# oblatkovac.net
KiCad netlist of a schematic drawn in EAGLE
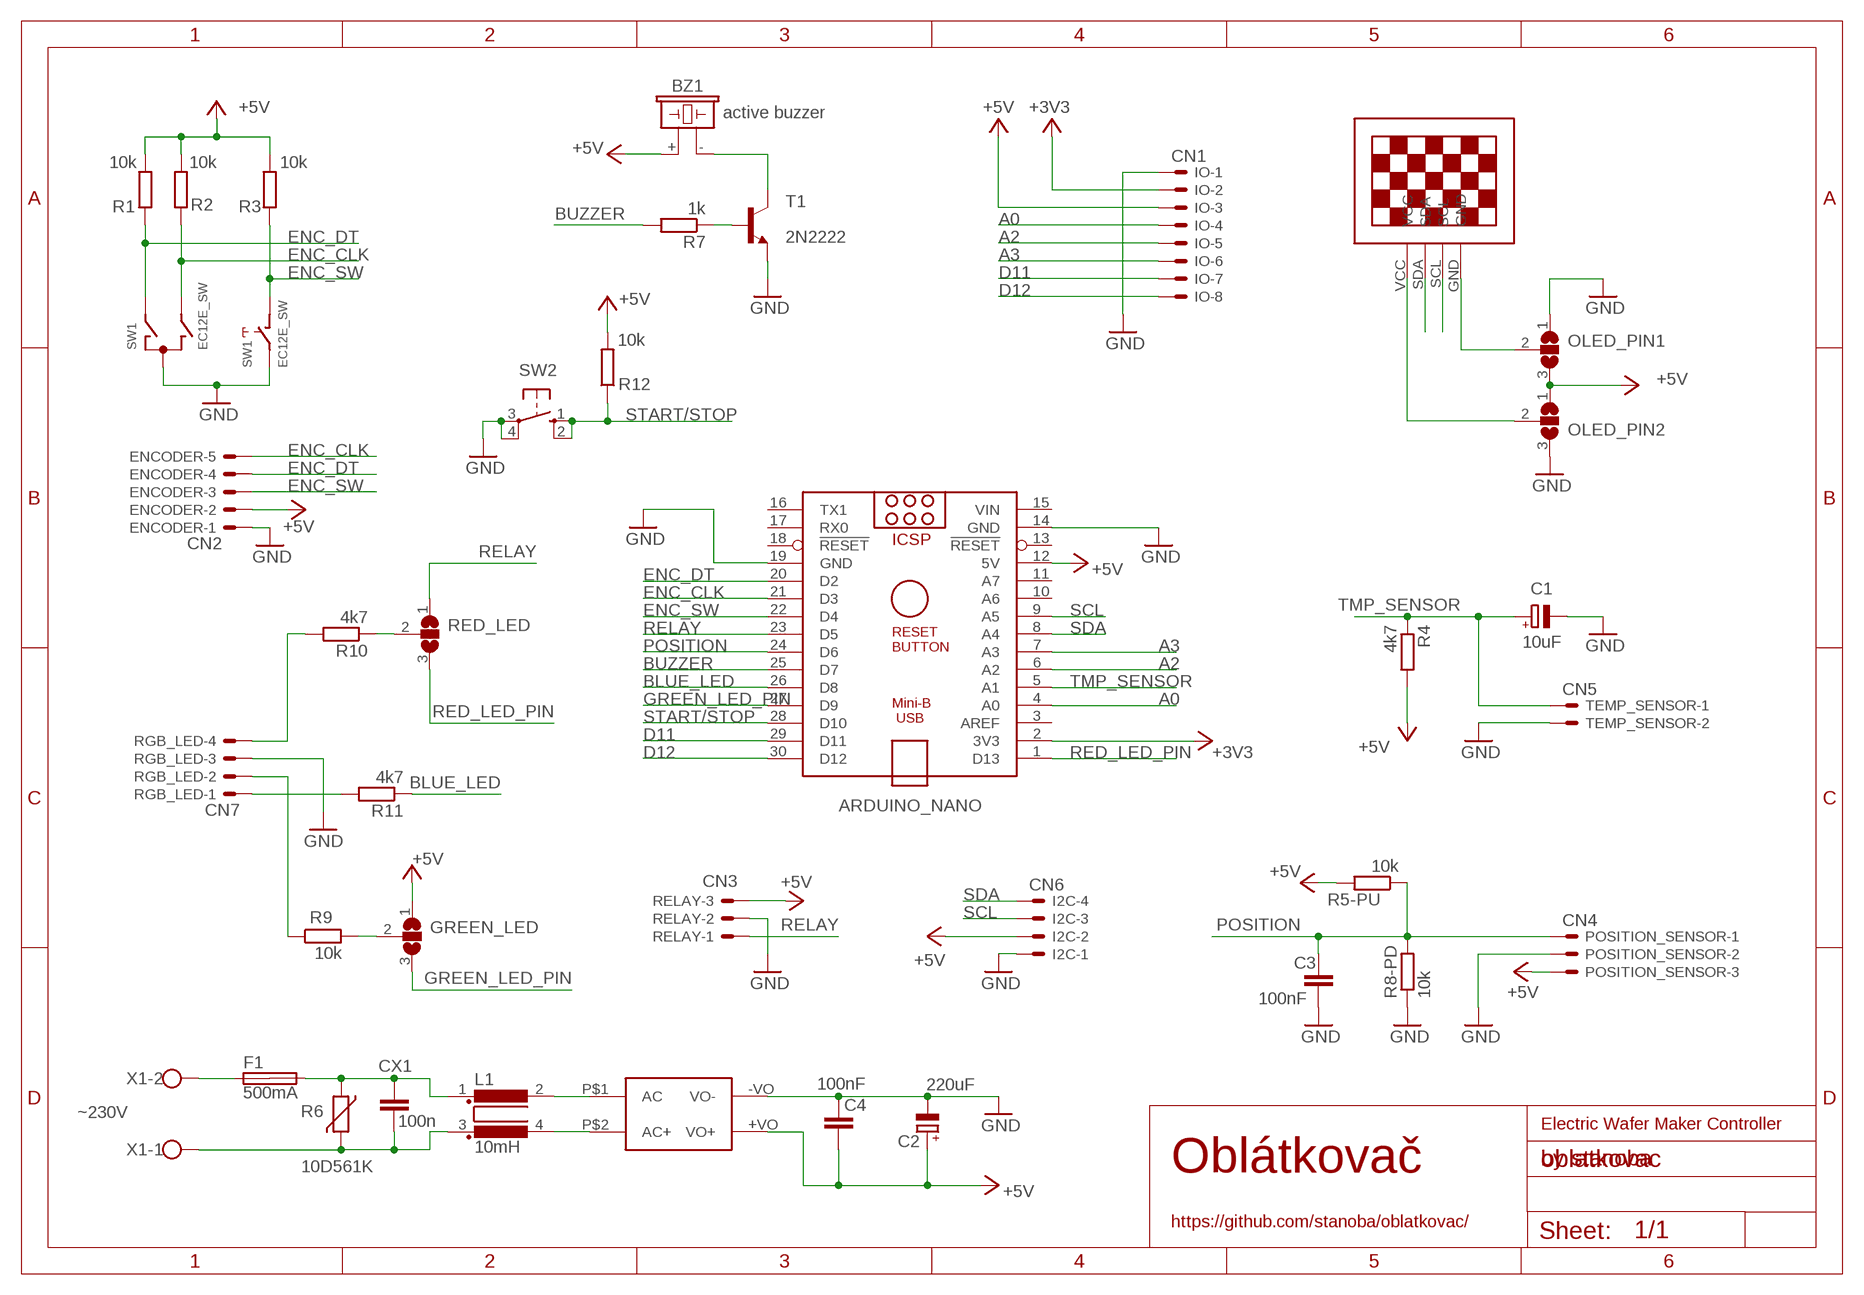
[diagram p0: schematic, sheet 1]

(export (version "E")
  (design (tool "Eeschema 10.0.6"))
  (components
    (comp (ref "ARDUINO_NANO")
      (value "ARDUINO_NANO")
      (footprint "eagle-import:ARDUINO_NANO")
      (libsource (lib "eagle-import") (part "ARDUINO_NANO"))
    )
    (comp (ref "BZ1")
      (value "active buzzer")
      (footprint "eagle-import:F_CM12P")
      (libsource (lib "eagle-import") (part "F/CM12P"))
    )
    (comp (ref "C1")
      (value "10uF")
      (footprint "eagle-import:E5-6")
      (libsource (lib "eagle-import") (part "CPOL-EUE5-6"))
    )
    (comp (ref "C2")
      (value "220uF")
      (footprint "eagle-import:E5-10,5")
      (libsource (lib "eagle-import") (part "CPOL-EUE5-10.5"))
    )
    (comp (ref "C3")
      (value "100nF")
      (footprint "eagle-import:C050-024X044")
      (libsource (lib "eagle-import") (part "C-EU050-024X044"))
    )
    (comp (ref "C4")
      (value "100nF")
      (footprint "eagle-import:C050-024X044")
      (libsource (lib "eagle-import") (part "C-EU050-024X044"))
    )
    (comp (ref "CX1")
      (value "100n")
      (footprint "eagle-import:XC10B6")
      (libsource (lib "eagle-import") (part "CXXC10B6"))
    )
    (comp (ref "ENCODER")
      (value "CN2")
      (footprint "eagle-import:JST-XH-05-PACKAGE-LONG-PAD")
      (libsource (lib "eagle-import") (part "JST-XH-05-PIN-LONG-PAD"))
    )
    (comp (ref "F1")
      (value "500mA")
      (footprint "eagle-import:SHK20L")
      (libsource (lib "eagle-import") (part "SHK20L"))
    )
    (comp (ref "GREEN_LED")
      (value "SJ2W")
      (footprint "eagle-import:SJ_2")
      (libsource (lib "eagle-import") (part "SJ2W"))
    )
    (comp (ref "I2C")
      (value "CN6")
      (footprint "eagle-import:JST-XH-04-PACKAGE-LONG-PAD")
      (libsource (lib "eagle-import") (part "JST-XH-04-PIN-LONG-PAD"))
    )
    (comp (ref "IO")
      (value "CN1")
      (footprint "eagle-import:JST-XH-08-PACKAGE-LONG-PAD")
      (libsource (lib "eagle-import") (part "JST-XH-08-PIN-LONG-PAD"))
    )
    (comp (ref "L1")
      (value "10mH")
      (footprint "eagle-import:B2")
      (libsource (lib "eagle-import") (part "R1405XB2"))
    )
    (comp (ref "OLED_PIN1")
      (value "SJ2W")
      (footprint "eagle-import:SJ_2")
      (libsource (lib "eagle-import") (part "SJ2W"))
    )
    (comp (ref "OLED_PIN2")
      (value "SJ2W")
      (footprint "eagle-import:SJ_2")
      (libsource (lib "eagle-import") (part "SJ2W"))
    )
    (comp (ref "POSITION_SENSOR")
      (value "CN4")
      (footprint "eagle-import:JST-XH-03-PACKAGE-LONG-PAD")
      (libsource (lib "eagle-import") (part "JST-XH-03-PIN-LONG-PAD"))
    )
    (comp (ref "R1")
      (value "10k")
      (footprint "eagle-import:0207_10")
      (libsource (lib "eagle-import") (part "R-EU_0207/10"))
    )
    (comp (ref "R2")
      (value "10k")
      (footprint "eagle-import:0207_10")
      (libsource (lib "eagle-import") (part "R-EU_0207/10"))
    )
    (comp (ref "R3")
      (value "10k")
      (footprint "eagle-import:0207_10")
      (libsource (lib "eagle-import") (part "R-EU_0207/10"))
    )
    (comp (ref "R4")
      (value "4k7")
      (footprint "eagle-import:0207_10")
      (libsource (lib "eagle-import") (part "R-EU_0207/10"))
    )
    (comp (ref "R5-PU")
      (value "10k")
      (footprint "eagle-import:0207_10")
      (libsource (lib "eagle-import") (part "R-EU_0207/10"))
    )
    (comp (ref "R6")
      (value "10D561K")
      (footprint "eagle-import:R-7,5")
      (libsource (lib "eagle-import") (part "VARISTOR-7,5"))
    )
    (comp (ref "R7")
      (value "1k")
      (footprint "eagle-import:0207_10")
      (libsource (lib "eagle-import") (part "R-EU_0207/10"))
    )
    (comp (ref "R8-PD")
      (value "10k")
      (footprint "eagle-import:0207_10")
      (libsource (lib "eagle-import") (part "R-EU_0207/10"))
    )
    (comp (ref "R9")
      (value "10k")
      (footprint "eagle-import:0207_10")
      (libsource (lib "eagle-import") (part "R-EU_0207/10"))
    )
    (comp (ref "R10")
      (value "4k7")
      (footprint "eagle-import:0207_10")
      (libsource (lib "eagle-import") (part "R-EU_0207/10"))
    )
    (comp (ref "R11")
      (value "4k7")
      (footprint "eagle-import:0207_10")
      (libsource (lib "eagle-import") (part "R-EU_0207/10"))
    )
    (comp (ref "R12")
      (value "10k")
      (footprint "eagle-import:0207_10")
      (libsource (lib "eagle-import") (part "R-EU_0207/10"))
    )
    (comp (ref "RED_LED")
      (value "SJ2W")
      (footprint "eagle-import:SJ_2")
      (libsource (lib "eagle-import") (part "SJ2W"))
    )
    (comp (ref "RELAY")
      (value "CN3")
      (footprint "eagle-import:JST-XH-03-PACKAGE-LONG-PAD")
      (libsource (lib "eagle-import") (part "JST-XH-03-PIN-LONG-PAD"))
    )
    (comp (ref "RGB_LED")
      (value "CN7")
      (footprint "eagle-import:JST-XH-04-PACKAGE-LONG-PAD")
      (libsource (lib "eagle-import") (part "JST-XH-04-PIN-LONG-PAD"))
    )
    (comp (ref "SW1")
      (value "EC12E_SW")
      (footprint "eagle-import:ALPS_EC12E_SW")
      (fields (field (name "MPN") "EC12E2424407"))
      (libsource (lib "eagle-import") (part "EC12E_SW"))
    )
    (comp (ref "SW2")
      (value "10-XX")
      (footprint "eagle-import:B3F-10XX")
      (fields (field (name "MPN") "B3F-1000"))
      (libsource (lib "eagle-import") (part "10-XX"))
    )
    (comp (ref "T1")
      (value "2N2222")
      (footprint "eagle-import:TO92-EBC")
      (libsource (lib "eagle-import") (part "-NPN-TO92-EBC"))
    )
    (comp (ref "TEMP_SENSOR")
      (value "CN5")
      (footprint "eagle-import:JST-XH-02-PACKAGE-LONG-PAD")
      (libsource (lib "eagle-import") (part "JST-XH-02-PIN-LONG-PAD"))
    )
    (comp (ref "U$1")
      (value "13\"OLED13\"OLED")
      (footprint "eagle-import:1.3_OLED")
      (libsource (lib "eagle-import") (part "13{dblquote}OLED13{dblquote}OLED"))
    )
    (comp (ref "U$2")
      (value "HLK-5M05")
      (footprint "eagle-import:HLK-5M05")
      (libsource (lib "eagle-import") (part "HLK-5M05"))
    )
    (comp (ref "X1")
      (value "~230V")
      (footprint "eagle-import:W237-102")
      (fields (field (name "MPN") "237-102"))
      (libsource (lib "eagle-import") (part "W237-102"))
    )
  )
  (nets
    (net (code "1") (name "+3V3") (class "Default")
      (node (ref "ARDUINO_NANO") (pin "2") (pinfunction "3V3_2") (pintype "output"))
      (node (ref "IO") (pin "2") (pinfunction "S_2") (pintype "passive"))
    )
    (net (code "2") (name "+5V") (class "Default")
      (node (ref "ARDUINO_NANO") (pin "12") (pinfunction "5V_12") (pintype "power_in"))
      (node (ref "BZ1") (pin "+") (pinfunction "1_+") (pintype "passive"))
      (node (ref "C2") (pin "+") (pinfunction "+_+") (pintype "passive"))
      (node (ref "C4") (pin "2") (pinfunction "2_2") (pintype "passive"))
      (node (ref "ENCODER") (pin "2") (pinfunction "S_2") (pintype "passive"))
      (node (ref "GREEN_LED") (pin "1") (pinfunction "1_1") (pintype "passive"))
      (node (ref "I2C") (pin "2") (pinfunction "S_2") (pintype "passive"))
      (node (ref "IO") (pin "3") (pinfunction "S_3") (pintype "passive"))
      (node (ref "OLED_PIN1") (pin "3") (pinfunction "3_3") (pintype "passive"))
      (node (ref "OLED_PIN2") (pin "1") (pinfunction "1_1") (pintype "passive"))
      (node (ref "POSITION_SENSOR") (pin "3") (pinfunction "S_3") (pintype "passive"))
      (node (ref "R1") (pin "2") (pinfunction "2_2") (pintype "passive"))
      (node (ref "R12") (pin "2") (pinfunction "2_2") (pintype "passive"))
      (node (ref "R2") (pin "2") (pinfunction "2_2") (pintype "passive"))
      (node (ref "R3") (pin "2") (pinfunction "2_2") (pintype "passive"))
      (node (ref "R4") (pin "2") (pinfunction "2_2") (pintype "passive"))
      (node (ref "R5-PU") (pin "2") (pinfunction "2_2") (pintype "passive"))
      (node (ref "RELAY") (pin "3") (pinfunction "S_3") (pintype "passive"))
      (node (ref "U$2") (pin "+VO") (pinfunction "VO+_+VO") (pintype "bidirectional"))
    )
    (net (code "3") (name "/A0") (class "Default")
      (node (ref "ARDUINO_NANO") (pin "4") (pinfunction "A0_4") (pintype "bidirectional"))
      (node (ref "IO") (pin "4") (pinfunction "S_4") (pintype "passive"))
    )
    (net (code "4") (name "/A2") (class "Default")
      (node (ref "ARDUINO_NANO") (pin "6") (pinfunction "A2_6") (pintype "bidirectional"))
      (node (ref "IO") (pin "5") (pinfunction "S_5") (pintype "passive"))
    )
    (net (code "5") (name "/A3") (class "Default")
      (node (ref "ARDUINO_NANO") (pin "7") (pinfunction "A3_7") (pintype "bidirectional"))
      (node (ref "IO") (pin "6") (pinfunction "S_6") (pintype "passive"))
    )
    (net (code "6") (name "/BLUE_LED") (class "Default")
      (node (ref "ARDUINO_NANO") (pin "26") (pinfunction "D8_26") (pintype "bidirectional"))
      (node (ref "R11") (pin "1") (pinfunction "1_1") (pintype "passive"))
    )
    (net (code "7") (name "/BUZZER") (class "Default")
      (node (ref "ARDUINO_NANO") (pin "25") (pinfunction "D7_25") (pintype "bidirectional"))
      (node (ref "R7") (pin "2") (pinfunction "2_2") (pintype "passive"))
    )
    (net (code "8") (name "/D11") (class "Default")
      (node (ref "ARDUINO_NANO") (pin "29") (pinfunction "D11_29") (pintype "bidirectional"))
      (node (ref "IO") (pin "7") (pinfunction "S_7") (pintype "passive"))
    )
    (net (code "9") (name "/D12") (class "Default")
      (node (ref "ARDUINO_NANO") (pin "30") (pinfunction "D12_30") (pintype "bidirectional"))
      (node (ref "IO") (pin "8") (pinfunction "S_8") (pintype "passive"))
    )
    (net (code "10") (name "/ENC_CLK") (class "Default")
      (node (ref "ARDUINO_NANO") (pin "21") (pinfunction "D3_21") (pintype "bidirectional"))
      (node (ref "ENCODER") (pin "5") (pinfunction "S_5") (pintype "passive"))
      (node (ref "R2") (pin "1") (pinfunction "1_1") (pintype "passive"))
      (node (ref "SW1") (pin "B") (pinfunction "B_B") (pintype "passive"))
    )
    (net (code "11") (name "/ENC_DT") (class "Default")
      (node (ref "ARDUINO_NANO") (pin "20") (pinfunction "D2_20") (pintype "bidirectional"))
      (node (ref "ENCODER") (pin "4") (pinfunction "S_4") (pintype "passive"))
      (node (ref "R1") (pin "1") (pinfunction "1_1") (pintype "passive"))
      (node (ref "SW1") (pin "A") (pinfunction "A_A") (pintype "passive"))
    )
    (net (code "12") (name "/ENC_SW") (class "Default")
      (node (ref "ARDUINO_NANO") (pin "22") (pinfunction "D4_22") (pintype "bidirectional"))
      (node (ref "ENCODER") (pin "3") (pinfunction "S_3") (pintype "passive"))
      (node (ref "R3") (pin "1") (pinfunction "1_1") (pintype "passive"))
      (node (ref "SW1") (pin "D") (pinfunction "1_D") (pintype "passive"))
    )
    (net (code "13") (name "/GREEN_LED_PIN") (class "Default")
      (node (ref "ARDUINO_NANO") (pin "27") (pinfunction "D9_27") (pintype "bidirectional"))
      (node (ref "GREEN_LED") (pin "3") (pinfunction "3_3") (pintype "passive"))
    )
    (net (code "14") (name "/POSITION") (class "Default")
      (node (ref "ARDUINO_NANO") (pin "24") (pinfunction "D6_24") (pintype "bidirectional"))
      (node (ref "C3") (pin "1") (pinfunction "1_1") (pintype "passive"))
      (node (ref "POSITION_SENSOR") (pin "1") (pinfunction "S_1") (pintype "passive"))
      (node (ref "R5-PU") (pin "1") (pinfunction "1_1") (pintype "passive"))
      (node (ref "R8-PD") (pin "2") (pinfunction "2_2") (pintype "passive"))
    )
    (net (code "15") (name "/RED_LED_PIN") (class "Default")
      (node (ref "ARDUINO_NANO") (pin "1") (pinfunction "D13_1") (pintype "bidirectional"))
      (node (ref "RED_LED") (pin "3") (pinfunction "3_3") (pintype "passive"))
    )
    (net (code "16") (name "/RELAY") (class "Default")
      (node (ref "ARDUINO_NANO") (pin "23") (pinfunction "D5_23") (pintype "bidirectional"))
      (node (ref "RED_LED") (pin "1") (pinfunction "1_1") (pintype "passive"))
      (node (ref "RELAY") (pin "1") (pinfunction "S_1") (pintype "passive"))
    )
    (net (code "17") (name "/SCL") (class "Default")
      (node (ref "ARDUINO_NANO") (pin "9") (pinfunction "A5_9") (pintype "bidirectional"))
      (node (ref "I2C") (pin "3") (pinfunction "S_3") (pintype "passive"))
      (node (ref "U$1") (pin "SCL") (pinfunction "SCL_SCL") (pintype "bidirectional"))
    )
    (net (code "18") (name "/SDA") (class "Default")
      (node (ref "ARDUINO_NANO") (pin "8") (pinfunction "A4_8") (pintype "bidirectional"))
      (node (ref "I2C") (pin "4") (pinfunction "S_4") (pintype "passive"))
      (node (ref "U$1") (pin "SDA") (pinfunction "SDA_SDA") (pintype "bidirectional"))
    )
    (net (code "19") (name "/START{slash}STOP") (class "Default")
      (node (ref "ARDUINO_NANO") (pin "28") (pinfunction "D10_28") (pintype "bidirectional"))
      (node (ref "R12") (pin "1") (pinfunction "1_1") (pintype "passive"))
      (node (ref "SW2") (pin "1") (pinfunction "S_1") (pintype "passive"))
      (node (ref "SW2") (pin "2") (pinfunction "S1_2") (pintype "passive"))
    )
    (net (code "20") (name "/TMP_SENSOR") (class "Default")
      (node (ref "ARDUINO_NANO") (pin "5") (pinfunction "A1_5") (pintype "bidirectional"))
      (node (ref "C1") (pin "+") (pinfunction "+_+") (pintype "passive"))
      (node (ref "R4") (pin "1") (pinfunction "1_1") (pintype "passive"))
      (node (ref "TEMP_SENSOR") (pin "1") (pinfunction "S_1") (pintype "passive"))
    )
    (net (code "21") (name "/VIN") (class "Default")
      (node (ref "ARDUINO_NANO") (pin "15") (pinfunction "VIN_15") (pintype "power_in"))
    )
    (net (code "22") (name "GND") (class "Default")
      (node (ref "ARDUINO_NANO") (pin "14") (pinfunction "GND_14") (pintype "power_in"))
      (node (ref "ARDUINO_NANO") (pin "19") (pinfunction "GND_19") (pintype "power_in"))
      (node (ref "C1") (pin "-") (pinfunction "-_-") (pintype "passive"))
      (node (ref "C2") (pin "-") (pinfunction "-_-") (pintype "passive"))
      (node (ref "C3") (pin "2") (pinfunction "2_2") (pintype "passive"))
      (node (ref "C4") (pin "1") (pinfunction "1_1") (pintype "passive"))
      (node (ref "ENCODER") (pin "1") (pinfunction "S_1") (pintype "passive"))
      (node (ref "I2C") (pin "1") (pinfunction "S_1") (pintype "passive"))
      (node (ref "IO") (pin "1") (pinfunction "S_1") (pintype "passive"))
      (node (ref "OLED_PIN1") (pin "1") (pinfunction "1_1") (pintype "passive"))
      (node (ref "OLED_PIN2") (pin "3") (pinfunction "3_3") (pintype "passive"))
      (node (ref "POSITION_SENSOR") (pin "2") (pinfunction "S_2") (pintype "passive"))
      (node (ref "R8-PD") (pin "1") (pinfunction "1_1") (pintype "passive"))
      (node (ref "RELAY") (pin "2") (pinfunction "S_2") (pintype "passive"))
      (node (ref "RGB_LED") (pin "3") (pinfunction "S_3") (pintype "passive"))
      (node (ref "SW1") (pin "C") (pinfunction "C_C") (pintype "passive"))
      (node (ref "SW1") (pin "E") (pinfunction "2_E") (pintype "passive"))
      (node (ref "SW2") (pin "3") (pinfunction "P_3") (pintype "passive"))
      (node (ref "SW2") (pin "4") (pinfunction "P1_4") (pintype "passive"))
      (node (ref "T1") (pin "E") (pinfunction "E_E") (pintype "passive"))
      (node (ref "TEMP_SENSOR") (pin "2") (pinfunction "S_2") (pintype "passive"))
      (node (ref "U$2") (pin "-VO") (pinfunction "VO-_-VO") (pintype "bidirectional"))
    )
    (net (code "23") (name "Net-(BZ1-2)") (class "Default")
      (node (ref "BZ1") (pin "-") (pinfunction "2_-") (pintype "passive"))
      (node (ref "T1") (pin "C") (pinfunction "C_C") (pintype "passive"))
    )
    (net (code "24") (name "Net-(CX1-Pad1)") (class "Default")
      (node (ref "CX1") (pin "1") (pinfunction "1_1") (pintype "passive"))
      (node (ref "F1") (pin "2A") (pinfunction "2A_2A") (pintype "passive"))
      (node (ref "L1") (pin "1") (pinfunction "1_1") (pintype "passive"))
      (node (ref "R6") (pin "1") (pinfunction "1_1") (pintype "passive"))
    )
    (net (code "25") (name "Net-(GREEN_LED-Pad2)") (class "Default")
      (node (ref "GREEN_LED") (pin "2") (pinfunction "2_2") (pintype "passive"))
      (node (ref "R9") (pin "2") (pinfunction "2_2") (pintype "passive"))
    )
    (net (code "26") (name "Net-(OLED_PIN1-Pad2)") (class "Default")
      (node (ref "OLED_PIN1") (pin "2") (pinfunction "2_2") (pintype "passive"))
      (node (ref "U$1") (pin "GND") (pinfunction "GND_GND") (pintype "bidirectional"))
    )
    (net (code "27") (name "Net-(OLED_PIN2-Pad2)") (class "Default")
      (node (ref "OLED_PIN2") (pin "2") (pinfunction "2_2") (pintype "passive"))
      (node (ref "U$1") (pin "VCC") (pinfunction "VCC_VCC") (pintype "bidirectional"))
    )
    (net (code "28") (name "Net-(R7-Pad1)") (class "Default")
      (node (ref "R7") (pin "1") (pinfunction "1_1") (pintype "passive"))
      (node (ref "T1") (pin "B") (pinfunction "B_B") (pintype "passive"))
    )
    (net (code "29") (name "Net-(R10-Pad1)") (class "Default")
      (node (ref "R10") (pin "1") (pinfunction "1_1") (pintype "passive"))
      (node (ref "RED_LED") (pin "2") (pinfunction "2_2") (pintype "passive"))
    )
    (net (code "30") (name "Net-(RGB_LEDA-S)") (class "Default")
      (node (ref "R11") (pin "2") (pinfunction "2_2") (pintype "passive"))
      (node (ref "RGB_LED") (pin "1") (pinfunction "S_1") (pintype "passive"))
    )
    (net (code "31") (name "Net-(RGB_LEDB-S)") (class "Default")
      (node (ref "R9") (pin "1") (pinfunction "1_1") (pintype "passive"))
      (node (ref "RGB_LED") (pin "2") (pinfunction "S_2") (pintype "passive"))
    )
    (net (code "32") (name "Net-(RGB_LEDD-S)") (class "Default")
      (node (ref "R10") (pin "2") (pinfunction "2_2") (pintype "passive"))
      (node (ref "RGB_LED") (pin "4") (pinfunction "S_4") (pintype "passive"))
    )
    (net (code "33") (name "Net-(U$2-AC)") (class "Default")
      (node (ref "L1") (pin "2") (pinfunction "2_2") (pintype "passive"))
      (node (ref "U$2") (pin "P$1") (pinfunction "AC_P$1") (pintype "bidirectional"))
    )
    (net (code "34") (name "Net-(U$2-AC+)") (class "Default")
      (node (ref "L1") (pin "4") (pinfunction "4_4") (pintype "passive"))
      (node (ref "U$2") (pin "P$2") (pinfunction "AC+_P$2") (pintype "bidirectional"))
    )
    (net (code "35") (name "Net-(X1A-KL)") (class "Default")
      (node (ref "CX1") (pin "2") (pinfunction "2_2") (pintype "passive"))
      (node (ref "L1") (pin "3") (pinfunction "3_3") (pintype "passive"))
      (node (ref "R6") (pin "2") (pinfunction "2_2") (pintype "passive"))
      (node (ref "X1") (pin "1") (pinfunction "KL_1") (pintype "passive"))
    )
    (net (code "36") (name "Net-(X1B-KL)") (class "Default")
      (node (ref "F1") (pin "1A") (pinfunction "1A_1A") (pintype "passive"))
      (node (ref "X1") (pin "2") (pinfunction "KL_2") (pintype "passive"))
    )
    (net (code "37") (name "unconnected-(ARDUINO_NANO-A6-Pad10)") (class "Default")
      (node (ref "ARDUINO_NANO") (pin "10") (pinfunction "A6_10") (pintype "bidirectional"))
    )
    (net (code "38") (name "unconnected-(ARDUINO_NANO-A7-Pad11)") (class "Default")
      (node (ref "ARDUINO_NANO") (pin "11") (pinfunction "A7_11") (pintype "bidirectional"))
    )
    (net (code "39") (name "unconnected-(ARDUINO_NANO-AREF-Pad3)") (class "Default")
      (node (ref "ARDUINO_NANO") (pin "3") (pinfunction "AREF_3") (pintype "input"))
    )
    (net (code "40") (name "unconnected-(ARDUINO_NANO-RX0-Pad17)") (class "Default")
      (node (ref "ARDUINO_NANO") (pin "17") (pinfunction "RX0_17") (pintype "bidirectional"))
    )
    (net (code "41") (name "unconnected-(ARDUINO_NANO-TX1-Pad16)") (class "Default")
      (node (ref "ARDUINO_NANO") (pin "16") (pinfunction "TX1_16") (pintype "bidirectional"))
    )
    (net (code "42") (name "unconnected-(ARDUINO_NANO-~{RESET}-Pad13)") (class "Default")
      (node (ref "ARDUINO_NANO") (pin "13") (pinfunction "~{RESET}_13") (pintype "input"))
    )
    (net (code "43") (name "unconnected-(ARDUINO_NANO-~{RESET}-Pad18)") (class "Default")
      (node (ref "ARDUINO_NANO") (pin "18") (pinfunction "~{RESET}_18") (pintype "input"))
    )
    (net (code "44") (name "unconnected-(F1-Pad1B)") (class "Default")
      (node (ref "F1") (pin "1B") (pinfunction "1B_1B") (pintype "passive"))
    )
    (net (code "45") (name "unconnected-(F1-Pad2B)") (class "Default")
      (node (ref "F1") (pin "2B") (pinfunction "2B_2B") (pintype "passive"))
    )
  )
)
